# LOGIC.net
KiCad netlist of a schematic drawn in Altium Designer
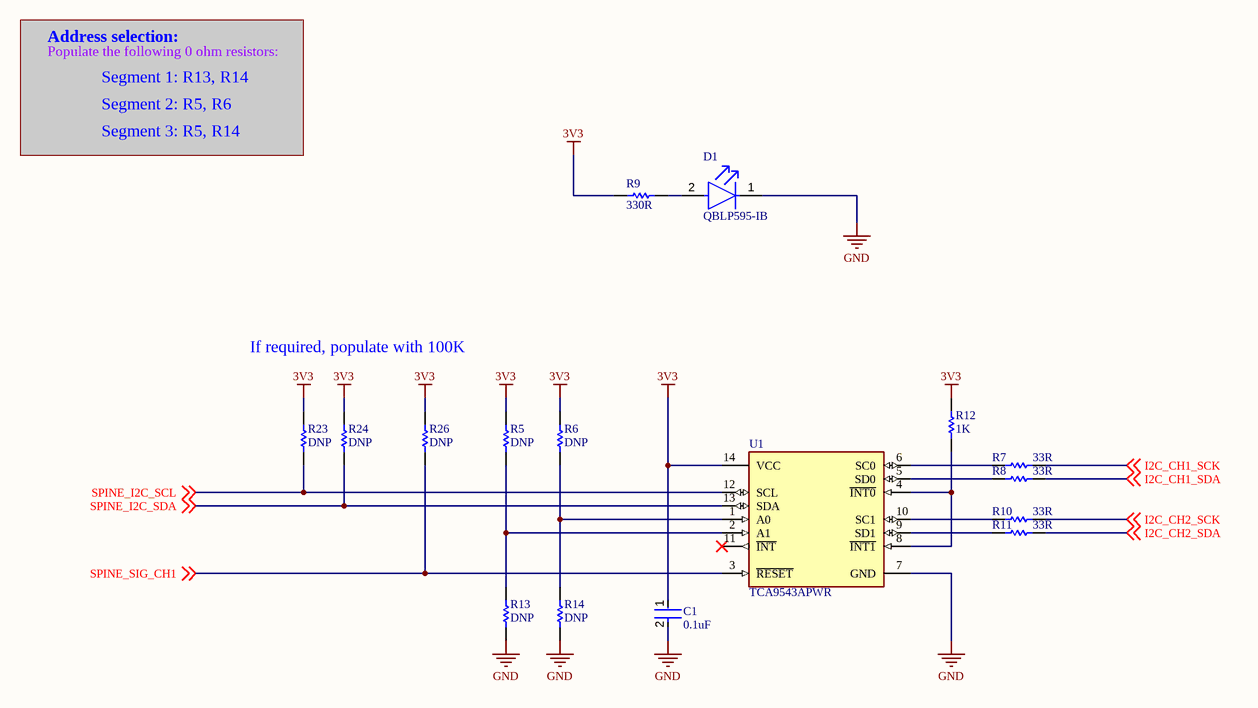
[diagram p0: LOGIC.SchDoc]

(export (version "E")
  (design (tool "Eeschema 10.0.6"))
  (components
    (comp (ref "C1")
      (value "0.1uF")
      (footprint "FP-GRM15-MFG")
      (description "CAP CER 0.1UF 16V X7R 0402")
      (fields (field (name "MANUFACTURER PART NUMBER") "GRM155R71C104KA88D") (field (name "TOLERANCE") "10%"))
      (libsource (lib "Altium Content Vault") (part "236180d848d6139a670b325ea6854c9"))
    )
    (comp (ref "D1")
      (value "QBLP595-IB")
      (footprint "FP-QBLP595-IB-MFG")
      (description "LED BLUE CLEAR 0402 SMD")
      (libsource (lib "Altium Content Vault") (part "8706943c75ba83719d021d2fdc84c58"))
    )
    (comp (ref "R5")
      (value "DNP")
      (footprint "RESC1005X40X25NL05T10")
      (fields (field (name "MANUFACTURER") "Yageo / Phycomp") (field (name "PART NUMBER") "RC0402JR-070RL"))
      (libsource (lib "Altium Content Vault") (part "RES"))
    )
    (comp (ref "R6")
      (value "DNP")
      (footprint "RESC1005X40X25NL05T10")
      (fields (field (name "MANUFACTURER") "Yageo / Phycomp") (field (name "PART NUMBER") "RC0402JR-070RL"))
      (libsource (lib "Altium Content Vault") (part "RES"))
    )
    (comp (ref "R7")
      (value "33R")
      (footprint "RESC1005X40X25LL05T05")
      (fields (field (name "MANUFACTURER") "Panasonic") (field (name "PART NUMBER") "ERJ2RKF33R0X"))
      (libsource (lib "Altium Content Vault") (part "RES"))
    )
    (comp (ref "R8")
      (value "33R")
      (footprint "RESC1005X40X25LL05T05")
      (fields (field (name "MANUFACTURER") "Panasonic") (field (name "PART NUMBER") "ERJ2RKF33R0X"))
      (libsource (lib "Altium Content Vault") (part "RES"))
    )
    (comp (ref "R9")
      (value "330R")
      (footprint "RESC1005X40X25NL05T10")
      (fields (field (name "PART NUMBER") "RC0402JR-07330RL") (field (name "MANUFACTURER") "Yageo / Phycomp"))
      (libsource (lib "Altium Content Vault") (part "RES"))
    )
    (comp (ref "R10")
      (value "33R")
      (footprint "RESC1005X40X25LL05T05")
      (fields (field (name "MANUFACTURER") "Panasonic") (field (name "PART NUMBER") "ERJ2RKF33R0X"))
      (libsource (lib "Altium Content Vault") (part "RES"))
    )
    (comp (ref "R11")
      (value "33R")
      (footprint "RESC1005X40X25LL05T05")
      (fields (field (name "MANUFACTURER") "Panasonic") (field (name "PART NUMBER") "ERJ2RKF33R0X"))
      (libsource (lib "Altium Content Vault") (part "RES"))
    )
    (comp (ref "R12")
      (value "1K")
      (footprint "RESC1005X40X25LL05T10")
      (fields (field (name "PART NUMBER") "RC0402JR-071KL") (field (name "MANUFACTURER") "Yageo / Phycomp"))
      (libsource (lib "Altium Content Vault") (part "RES"))
    )
    (comp (ref "R13")
      (value "DNP")
      (footprint "RESC1005X40X25NL05T10")
      (fields (field (name "MANUFACTURER") "Yageo / Phycomp") (field (name "PART NUMBER") "RC0402JR-070RL"))
      (libsource (lib "Altium Content Vault") (part "RES"))
    )
    (comp (ref "R14")
      (value "DNP")
      (footprint "RESC1005X40X25NL05T10")
      (fields (field (name "MANUFACTURER") "Yageo / Phycomp") (field (name "PART NUMBER") "RC0402JR-070RL"))
      (libsource (lib "Altium Content Vault") (part "RES"))
    )
    (comp (ref "R23")
      (value "DNP")
      (footprint "RESC1005X40X25ML10T10")
      (fields (field (name "PART NUMBER") "ERA-2AED104X") (field (name "MANUFACTURER") "Panasonic"))
      (libsource (lib "Altium Content Vault") (part "RES"))
    )
    (comp (ref "R24")
      (value "DNP")
      (footprint "RESC1005X40X25ML10T10")
      (fields (field (name "PART NUMBER") "ERA-2AED104X") (field (name "MANUFACTURER") "Panasonic"))
      (libsource (lib "Altium Content Vault") (part "RES"))
    )
    (comp (ref "R26")
      (value "DNP")
      (footprint "RESC1005X40X25ML10T10")
      (fields (field (name "PART NUMBER") "ERA-2AED104X") (field (name "MANUFACTURER") "Panasonic"))
      (libsource (lib "Altium Content Vault") (part "RES"))
    )
    (comp (ref "U1")
      (value "TCA9543APWR")
      (footprint "FP-PW0014A-IPC_A")
      (description "IC BUS SWITCH 2 X 1:2 14TSSOP")
      (libsource (lib "Altium Content Vault") (part "ec732b84f4d0dac1d39e6b5ccaf9408"))
    )
  )
  (nets
    (net (code "1") (name "3V3") (class "Default")
      (node (ref "C1") (pin "1") (pinfunction "1_1") (pintype "passive"))
      (node (ref "R12") (pin "2") (pinfunction "2_2") (pintype "passive"))
      (node (ref "R23") (pin "2") (pinfunction "2_2") (pintype "passive"))
      (node (ref "R24") (pin "2") (pinfunction "2_2") (pintype "passive"))
      (node (ref "R26") (pin "2") (pinfunction "2_2") (pintype "passive"))
      (node (ref "R5") (pin "2") (pinfunction "2_2") (pintype "passive"))
      (node (ref "R6") (pin "2") (pinfunction "2_2") (pintype "passive"))
      (node (ref "R9") (pin "1") (pinfunction "1_1") (pintype "passive"))
      (node (ref "U1") (pin "14") (pinfunction "VCC_14") (pintype "power_in"))
    )
    (net (code "2") (name "GND") (class "Default")
      (node (ref "C1") (pin "2") (pinfunction "2_2") (pintype "passive"))
      (node (ref "D1") (pin "1") (pinfunction "C_1") (pintype "passive"))
      (node (ref "R13") (pin "1") (pinfunction "1_1") (pintype "passive"))
      (node (ref "R14") (pin "1") (pinfunction "1_1") (pintype "passive"))
      (node (ref "U1") (pin "7") (pinfunction "GND_7") (pintype "power_in"))
    )
    (net (code "3") (name "I2C_CH1_SCK") (class "Default")
      (node (ref "R7") (pin "2") (pinfunction "2_2") (pintype "passive"))
    )
    (net (code "4") (name "I2C_CH1_SDA") (class "Default")
      (node (ref "R8") (pin "2") (pinfunction "2_2") (pintype "passive"))
    )
    (net (code "5") (name "I2C_CH2_SCK") (class "Default")
      (node (ref "R10") (pin "2") (pinfunction "2_2") (pintype "passive"))
    )
    (net (code "6") (name "I2C_CH2_SDA") (class "Default")
      (node (ref "R11") (pin "2") (pinfunction "2_2") (pintype "passive"))
    )
    (net (code "7") (name "Net-(D1-A)") (class "Default")
      (node (ref "D1") (pin "2") (pinfunction "A_2") (pintype "passive"))
      (node (ref "R9") (pin "2") (pinfunction "2_2") (pintype "passive"))
    )
    (net (code "8") (name "Net-(U1-A0)") (class "Default")
      (node (ref "R14") (pin "2") (pinfunction "2_2") (pintype "passive"))
      (node (ref "R6") (pin "1") (pinfunction "1_1") (pintype "passive"))
      (node (ref "U1") (pin "1") (pinfunction "A0_1") (pintype "input"))
    )
    (net (code "9") (name "Net-(U1-A1)") (class "Default")
      (node (ref "R13") (pin "2") (pinfunction "2_2") (pintype "passive"))
      (node (ref "R5") (pin "1") (pinfunction "1_1") (pintype "passive"))
      (node (ref "U1") (pin "2") (pinfunction "A1_2") (pintype "input"))
    )
    (net (code "10") (name "Net-(U1-SC0)") (class "Default")
      (node (ref "R7") (pin "1") (pinfunction "1_1") (pintype "passive"))
      (node (ref "U1") (pin "6") (pinfunction "SC0_6") (pintype "bidirectional"))
    )
    (net (code "11") (name "Net-(U1-SC1)") (class "Default")
      (node (ref "R10") (pin "1") (pinfunction "1_1") (pintype "passive"))
      (node (ref "U1") (pin "10") (pinfunction "SC1_10") (pintype "bidirectional"))
    )
    (net (code "12") (name "Net-(U1-SD0)") (class "Default")
      (node (ref "R8") (pin "1") (pinfunction "1_1") (pintype "passive"))
      (node (ref "U1") (pin "5") (pinfunction "SD0_5") (pintype "bidirectional"))
    )
    (net (code "13") (name "Net-(U1-SD1)") (class "Default")
      (node (ref "R11") (pin "1") (pinfunction "1_1") (pintype "passive"))
      (node (ref "U1") (pin "9") (pinfunction "SD1_9") (pintype "bidirectional"))
    )
    (net (code "14") (name "Net-(U1-~{INT0})") (class "Default")
      (node (ref "R12") (pin "1") (pinfunction "1_1") (pintype "passive"))
      (node (ref "U1") (pin "4") (pinfunction "~{INT0}_4") (pintype "input"))
      (node (ref "U1") (pin "8") (pinfunction "~{INT1}_8") (pintype "input"))
    )
    (net (code "15") (name "SPINE_I2C_SCL") (class "Default")
      (node (ref "R23") (pin "1") (pinfunction "1_1") (pintype "passive"))
      (node (ref "U1") (pin "12") (pinfunction "SCL_12") (pintype "bidirectional"))
    )
    (net (code "16") (name "SPINE_I2C_SDA") (class "Default")
      (node (ref "R24") (pin "1") (pinfunction "1_1") (pintype "passive"))
      (node (ref "U1") (pin "13") (pinfunction "SDA_13") (pintype "bidirectional"))
    )
    (net (code "17") (name "SPINE_SIG_CH1") (class "Default")
      (node (ref "R26") (pin "1") (pinfunction "1_1") (pintype "passive"))
      (node (ref "U1") (pin "3") (pinfunction "~{RESET}_3") (pintype "input"))
    )
    (net (code "18") (name "unconnected-(U1-~{INT}-Pad11)") (class "Default")
      (node (ref "U1") (pin "11") (pinfunction "~{INT}_11") (pintype "output+no_connect"))
    )
  )
)
